# 100068622_payload_detect.net
KiCad netlist of a schematic drawn in Altium Designer
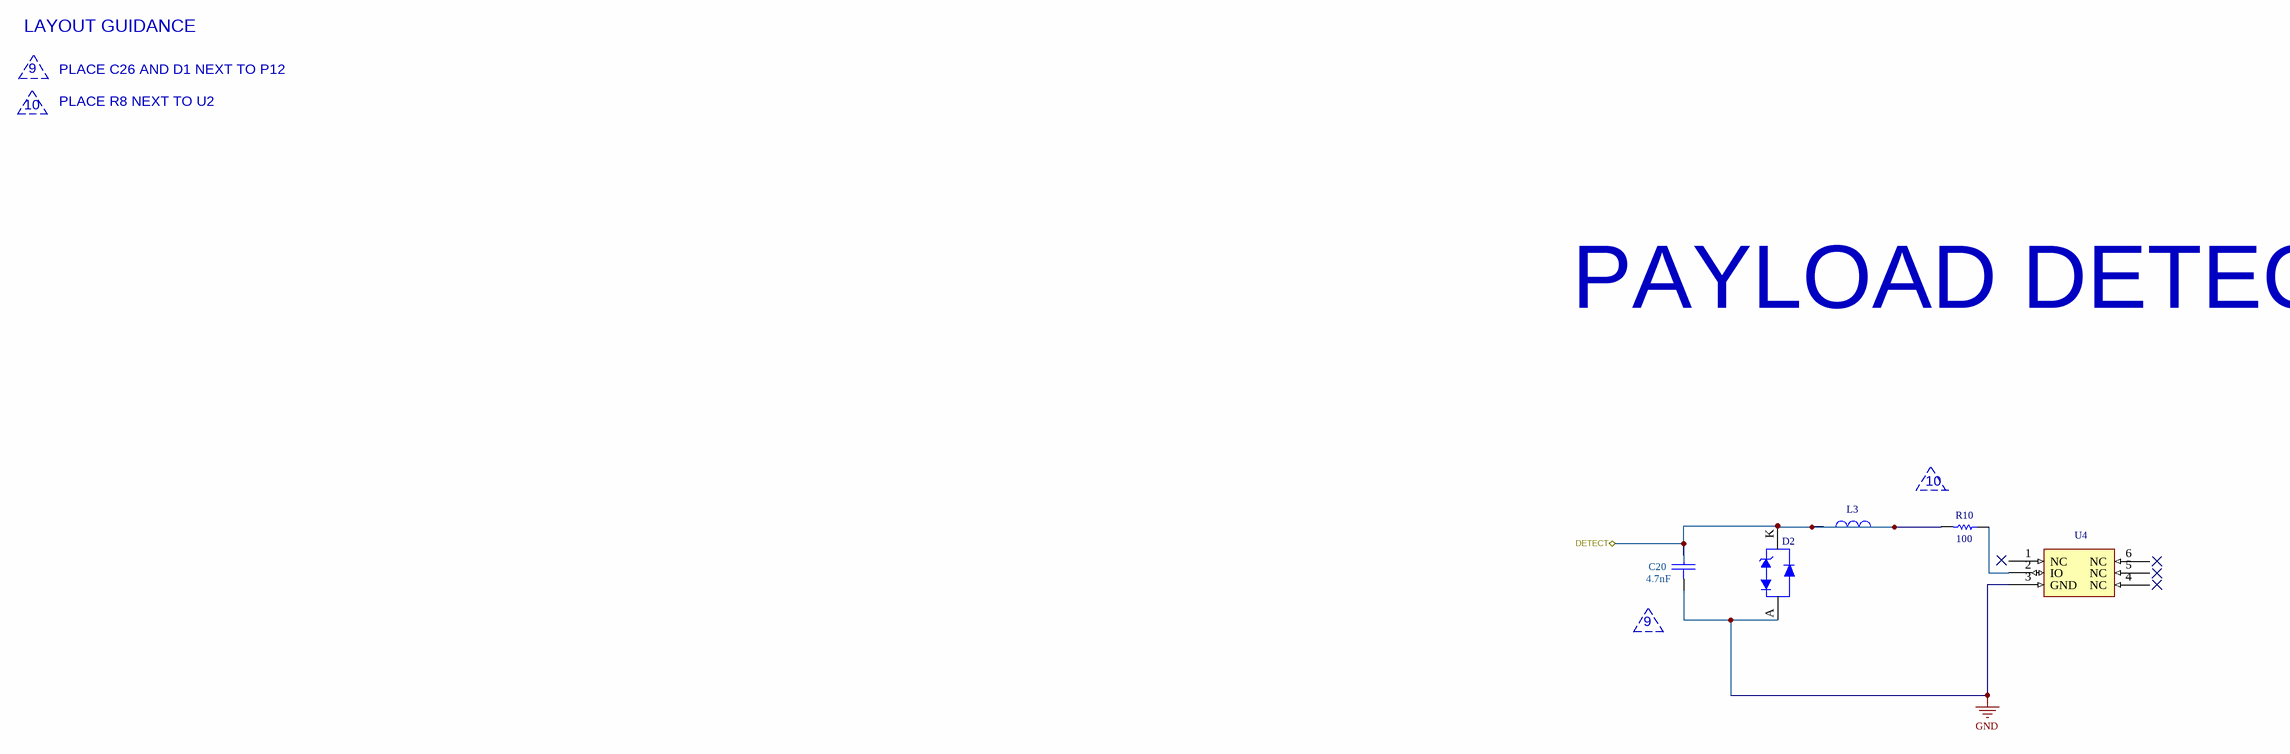
[diagram p0: 100068622_payload_detect.SchDoc]

(export (version "E")
  (design (tool "Eeschema 10.0.6"))
  (components
    (comp (ref "C20")
      (value "4.7nF")
      (footprint "CAP-0402-A")
      (description "CAP 0402 4700PF 50V 10% X7R")
      (fields (field (name "TOLERANCE") "10%"))
      (libsource (lib "Picatinny Server") (part "Capacitor - Non-Polarized"))
    )
    (comp (ref "D2")
      (value "SMF3.3")
      (footprint "DI-SOD123F-A")
      (description "ESD protection diodes / TVS diodes; LITTELFUSE; SMF3.3; 6.8 V; 30 A; 3.3 V; 3.4 V - 4.3 V")
      (libsource (lib "Picatinny Server") (part "Diode - TVS (Unidirectional)"))
    )
    (comp (ref "L3")
      (value "MDF2016BSS270C")
      (footprint "IND-0806-A")
      (description "Ferrite Bead, Aec-Q200, 0806, 1A Rohs Compliant: Yes")
      (libsource (lib "Picatinny Server") (part "Inductor"))
    )
    (comp (ref "R10")
      (value "100")
      (footprint "RES-0402-B")
      (description "Res 0402 100 Ohm 0.1W 1% Thick Film")
      (fields (field (name "POWER") "100mW") (field (name "TOLERANCE") "1%"))
      (libsource (lib "Picatinny Server") (part "Resistor"))
    )
    (comp (ref "U4")
      (value "DS2431Q-TR")
      (footprint "IC-TDFN3X3-B")
      (description "IC EEPROM 1KBIT 1-WIRE 6TDFN")
      (libsource (lib "Picatinny Server") (part "DS2431Q-TR"))
    )
  )
  (nets
    (net (code "1") (name "/DETECT") (class "Default")
      (node (ref "C20") (pin "2") (pinfunction "2_2") (pintype "passive"))
      (node (ref "D2") (pin "K") (pinfunction "K_K") (pintype "passive"))
      (node (ref "L3") (pin "1") (pinfunction "1_1") (pintype "passive"))
      (node (ref "L3") (pin "2") (pinfunction "2_2") (pintype "passive"))
      (node (ref "R10") (pin "1") (pinfunction "1_1") (pintype "passive"))
    )
    (net (code "2") (name "GND") (class "Default")
      (node (ref "C20") (pin "1") (pinfunction "1_1") (pintype "passive"))
      (node (ref "D2") (pin "A") (pinfunction "A_A") (pintype "passive"))
      (node (ref "U4") (pin "3") (pinfunction "GND_3") (pintype "input"))
    )
    (net (code "3") (name "Net-(U4-IO)") (class "Default")
      (node (ref "R10") (pin "2") (pinfunction "2_2") (pintype "passive"))
      (node (ref "U4") (pin "2") (pinfunction "IO_2") (pintype "bidirectional"))
    )
    (net (code "4") (name "unconnected-(U4-NC-Pad1)") (class "Default")
      (node (ref "U4") (pin "1") (pinfunction "NC_1") (pintype "input"))
    )
    (net (code "5") (name "unconnected-(U4-NC-Pad4)") (class "Default")
      (node (ref "U4") (pin "4") (pinfunction "NC_4") (pintype "input"))
    )
    (net (code "6") (name "unconnected-(U4-NC-Pad5)") (class "Default")
      (node (ref "U4") (pin "5") (pinfunction "NC_5") (pintype "input"))
    )
    (net (code "7") (name "unconnected-(U4-NC-Pad6)") (class "Default")
      (node (ref "U4") (pin "6") (pinfunction "NC_6") (pintype "input"))
    )
  )
)
